# main_board_without_pads.net
KiCad netlist of a schematic drawn in EAGLE
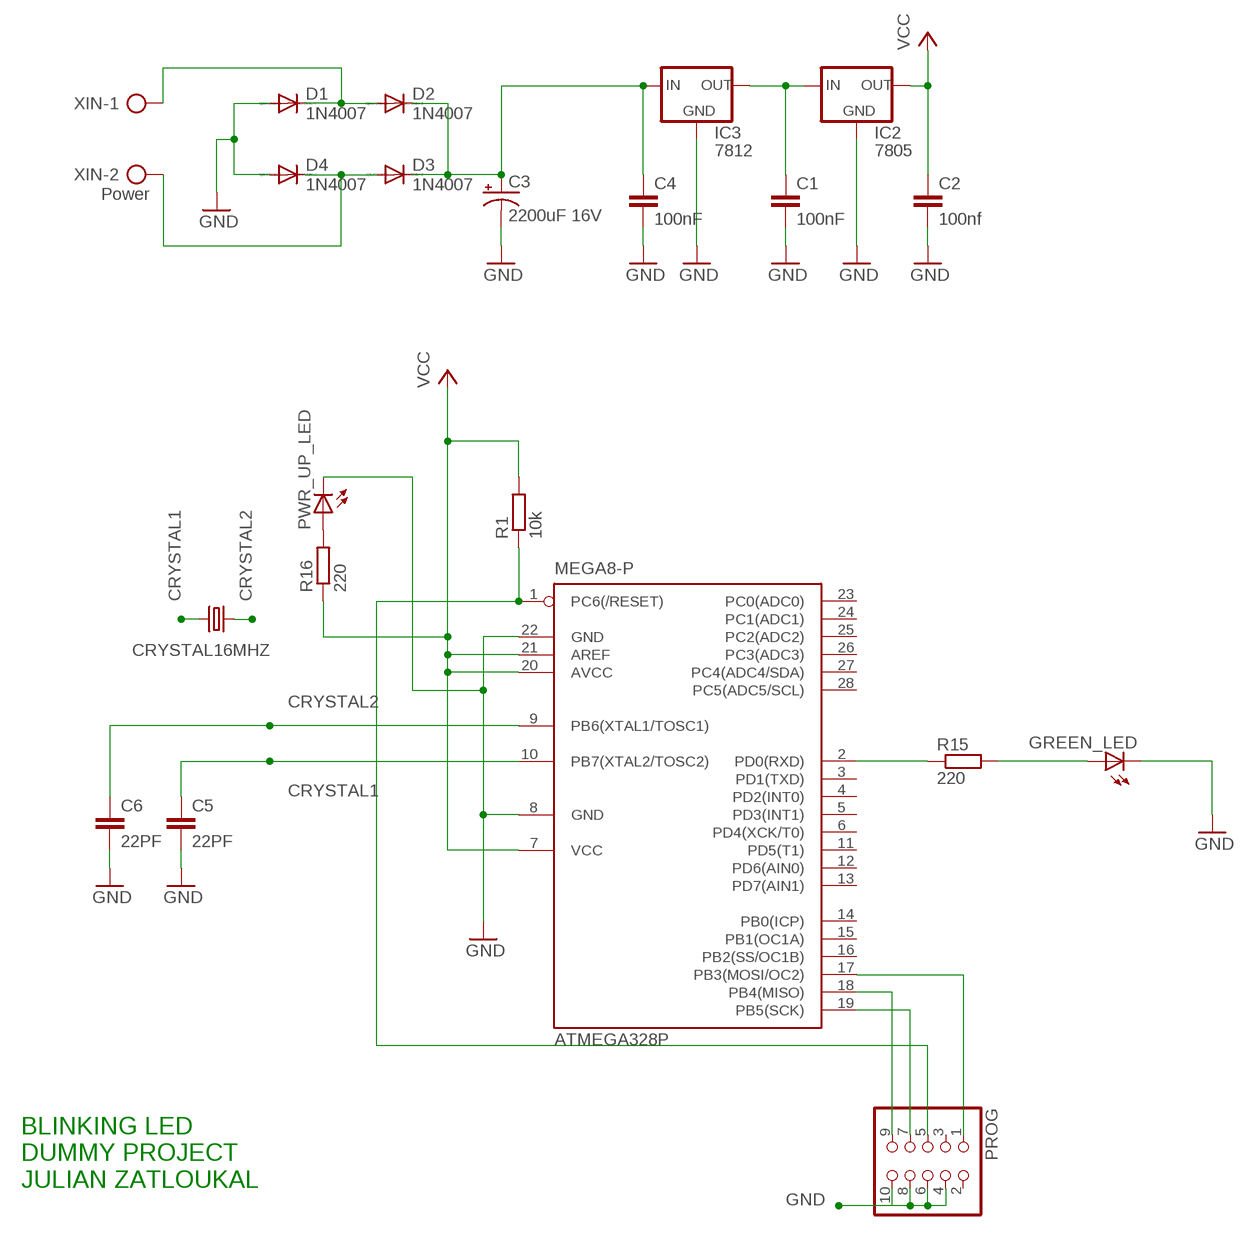
[diagram p0: schematic, sheet 1]

(export (version "E")
  (design (tool "Eeschema 10.0.6"))
  (components
    (comp (ref "ATMEGA328P")
      (value "MEGA8-P")
      (footprint "eagle-import:DIL28-3")
      (libsource (lib "eagle-import") (part "MEGA8-P"))
    )
    (comp (ref "C1")
      (value "100nF")
      (footprint "eagle-import:C050-025X075")
      (libsource (lib "eagle-import") (part "C-EU050-025X075"))
    )
    (comp (ref "C2")
      (value "100nf")
      (footprint "eagle-import:C050-025X075")
      (libsource (lib "eagle-import") (part "C-EU050-025X075"))
    )
    (comp (ref "C3")
      (value "2200uF 16V")
      (footprint "eagle-import:E7,5-16")
      (libsource (lib "eagle-import") (part "CPOL-USE7.5-16"))
    )
    (comp (ref "C4")
      (value "100nF")
      (footprint "eagle-import:C050-025X075")
      (libsource (lib "eagle-import") (part "C-EU050-025X075"))
    )
    (comp (ref "C5")
      (value "22PF")
      (footprint "eagle-import:C050-024X044")
      (libsource (lib "eagle-import") (part "C-EU050-024X044"))
    )
    (comp (ref "C6")
      (value "22PF")
      (footprint "eagle-import:C050-024X044")
      (libsource (lib "eagle-import") (part "C-EU050-024X044"))
    )
    (comp (ref "CRYSTAL16MHZ")
      (value "CRYSTALHC49S")
      (footprint "eagle-import:HC49_S")
      (libsource (lib "eagle-import") (part "CRYSTALHC49S"))
    )
    (comp (ref "D1")
      (value "1N4007")
      (footprint "eagle-import:DO41-10")
      (libsource (lib "eagle-import") (part "1N4004"))
    )
    (comp (ref "D2")
      (value "1N4007")
      (footprint "eagle-import:DO41-10")
      (libsource (lib "eagle-import") (part "1N4004"))
    )
    (comp (ref "D3")
      (value "1N4007")
      (footprint "eagle-import:DO41-10")
      (libsource (lib "eagle-import") (part "1N4004"))
    )
    (comp (ref "D4")
      (value "1N4007")
      (footprint "eagle-import:DO41-10")
      (libsource (lib "eagle-import") (part "1N4004"))
    )
    (comp (ref "GREEN_LED")
      (value "LED5MM")
      (footprint "eagle-import:LED5MM")
      (libsource (lib "eagle-import") (part "LED5MM"))
    )
    (comp (ref "IC2")
      (value "7805")
      (footprint "eagle-import:78XXL")
      (libsource (lib "eagle-import") (part "78XXL"))
    )
    (comp (ref "IC3")
      (value "7812")
      (footprint "eagle-import:78XXL")
      (libsource (lib "eagle-import") (part "78XXL"))
    )
    (comp (ref "PROG")
      (value "PINHD-2X5")
      (footprint "eagle-import:2X05")
      (libsource (lib "eagle-import") (part "PINHD-2X5"))
    )
    (comp (ref "PWR_UP_LED")
      (value "LED5MM")
      (footprint "eagle-import:LED5MM")
      (libsource (lib "eagle-import") (part "LED5MM"))
    )
    (comp (ref "R1")
      (value "10k")
      (footprint "eagle-import:0207_10")
      (libsource (lib "eagle-import") (part "R-EU_0207/10"))
    )
    (comp (ref "R15")
      (value "220")
      (footprint "eagle-import:0207_10")
      (libsource (lib "eagle-import") (part "R-EU_0207/10"))
    )
    (comp (ref "R16")
      (value "220")
      (footprint "eagle-import:0207_10")
      (libsource (lib "eagle-import") (part "rcl_334_R-EU_0207/10"))
    )
    (comp (ref "XIN")
      (value "Power")
      (footprint "eagle-import:AK500_2")
      (libsource (lib "eagle-import") (part "AK500/2"))
    )
  )
  (nets
    (net (code "1") (name "/CRYSTAL1") (class "Default")
      (node (ref "ATMEGA328P") (pin "10") (pinfunction "PB7(XTAL2/TOSC2)_10") (pintype "bidirectional"))
      (node (ref "C5") (pin "1") (pinfunction "1_1") (pintype "passive"))
      (node (ref "CRYSTAL16MHZ") (pin "2") (pinfunction "2_2") (pintype "passive"))
    )
    (net (code "2") (name "/CRYSTAL2") (class "Default")
      (node (ref "ATMEGA328P") (pin "9") (pinfunction "PB6(XTAL1/TOSC1)_9") (pintype "bidirectional"))
      (node (ref "C6") (pin "1") (pinfunction "1_1") (pintype "passive"))
      (node (ref "CRYSTAL16MHZ") (pin "1") (pinfunction "1_1") (pintype "passive"))
    )
    (net (code "3") (name "GND") (class "Default")
      (node (ref "ATMEGA328P") (pin "22") (pinfunction "GND_22") (pintype "power_in"))
      (node (ref "ATMEGA328P") (pin "8") (pinfunction "GND_8") (pintype "power_in"))
      (node (ref "C1") (pin "2") (pinfunction "2_2") (pintype "passive"))
      (node (ref "C2") (pin "2") (pinfunction "2_2") (pintype "passive"))
      (node (ref "C3") (pin "-") (pinfunction "-_-") (pintype "passive"))
      (node (ref "C4") (pin "2") (pinfunction "2_2") (pintype "passive"))
      (node (ref "C5") (pin "2") (pinfunction "2_2") (pintype "passive"))
      (node (ref "C6") (pin "2") (pinfunction "2_2") (pintype "passive"))
      (node (ref "D1") (pin "A") (pinfunction "A_A") (pintype "passive"))
      (node (ref "D4") (pin "A") (pinfunction "A_A") (pintype "passive"))
      (node (ref "GREEN_LED") (pin "K") (pinfunction "C_K") (pintype "passive"))
      (node (ref "IC2") (pin "GND") (pinfunction "GND_GND") (pintype "input"))
      (node (ref "IC3") (pin "GND") (pinfunction "GND_GND") (pintype "input"))
      (node (ref "PROG") (pin "10") (pinfunction "10_10") (pintype "passive"))
      (node (ref "PROG") (pin "4") (pinfunction "4_4") (pintype "passive"))
      (node (ref "PROG") (pin "6") (pinfunction "6_6") (pintype "passive"))
      (node (ref "PROG") (pin "8") (pinfunction "8_8") (pintype "passive"))
      (node (ref "PWR_UP_LED") (pin "K") (pinfunction "C_K") (pintype "passive"))
    )
    (net (code "4") (name "Net-(ATMEGA328P-PB3(MOSI{slash}OC2))") (class "Default")
      (node (ref "ATMEGA328P") (pin "17") (pinfunction "PB3(MOSI/OC2)_17") (pintype "bidirectional"))
      (node (ref "PROG") (pin "1") (pinfunction "1_1") (pintype "passive"))
    )
    (net (code "5") (name "Net-(ATMEGA328P-PB4(MISO))") (class "Default")
      (node (ref "ATMEGA328P") (pin "18") (pinfunction "PB4(MISO)_18") (pintype "bidirectional"))
      (node (ref "PROG") (pin "9") (pinfunction "9_9") (pintype "passive"))
    )
    (net (code "6") (name "Net-(ATMEGA328P-PB5(SCK))") (class "Default")
      (node (ref "ATMEGA328P") (pin "19") (pinfunction "PB5(SCK)_19") (pintype "bidirectional"))
      (node (ref "PROG") (pin "7") (pinfunction "7_7") (pintype "passive"))
    )
    (net (code "7") (name "Net-(ATMEGA328P-PC6({slash}RESET))") (class "Default")
      (node (ref "ATMEGA328P") (pin "1") (pinfunction "PC6(/RESET)_1") (pintype "bidirectional"))
      (node (ref "PROG") (pin "5") (pinfunction "5_5") (pintype "passive"))
      (node (ref "R1") (pin "1") (pinfunction "1_1") (pintype "passive"))
    )
    (net (code "8") (name "Net-(ATMEGA328P-PD0(RXD))") (class "Default")
      (node (ref "ATMEGA328P") (pin "2") (pinfunction "PD0(RXD)_2") (pintype "bidirectional"))
      (node (ref "R15") (pin "1") (pinfunction "1_1") (pintype "passive"))
    )
    (net (code "9") (name "Net-(C1-Pad1)") (class "Default")
      (node (ref "C1") (pin "1") (pinfunction "1_1") (pintype "passive"))
      (node (ref "IC2") (pin "IN") (pinfunction "IN_IN") (pintype "input"))
      (node (ref "IC3") (pin "OUT") (pinfunction "OUT_OUT") (pintype "passive"))
    )
    (net (code "10") (name "Net-(C3-Pad+)") (class "Default")
      (node (ref "C3") (pin "+") (pinfunction "+_+") (pintype "passive"))
      (node (ref "C4") (pin "1") (pinfunction "1_1") (pintype "passive"))
      (node (ref "D2") (pin "C") (pinfunction "C_C") (pintype "passive"))
      (node (ref "D3") (pin "C") (pinfunction "C_C") (pintype "passive"))
      (node (ref "IC3") (pin "IN") (pinfunction "IN_IN") (pintype "input"))
    )
    (net (code "11") (name "Net-(GREEN_LED-PadA)") (class "Default")
      (node (ref "GREEN_LED") (pin "A") (pinfunction "A_A") (pintype "passive"))
      (node (ref "R15") (pin "2") (pinfunction "2_2") (pintype "passive"))
    )
    (net (code "12") (name "Net-(PWR_UP_LED-PadA)") (class "Default")
      (node (ref "PWR_UP_LED") (pin "A") (pinfunction "A_A") (pintype "passive"))
      (node (ref "R16") (pin "2") (pinfunction "2_2") (pintype "passive"))
    )
    (net (code "13") (name "Net-(XINA-KL)") (class "Default")
      (node (ref "D1") (pin "C") (pinfunction "C_C") (pintype "passive"))
      (node (ref "D2") (pin "A") (pinfunction "A_A") (pintype "passive"))
      (node (ref "XIN") (pin "1") (pinfunction "KL_1") (pintype "passive"))
    )
    (net (code "14") (name "Net-(XINB-KL)") (class "Default")
      (node (ref "D3") (pin "A") (pinfunction "A_A") (pintype "passive"))
      (node (ref "D4") (pin "C") (pinfunction "C_C") (pintype "passive"))
      (node (ref "XIN") (pin "2") (pinfunction "KL_2") (pintype "passive"))
    )
    (net (code "15") (name "VCC") (class "Default")
      (node (ref "ATMEGA328P") (pin "20") (pinfunction "AVCC_20") (pintype "power_in"))
      (node (ref "ATMEGA328P") (pin "21") (pinfunction "AREF_21") (pintype "passive"))
      (node (ref "ATMEGA328P") (pin "7") (pinfunction "VCC_7") (pintype "power_in"))
      (node (ref "C2") (pin "1") (pinfunction "1_1") (pintype "passive"))
      (node (ref "IC2") (pin "OUT") (pinfunction "OUT_OUT") (pintype "passive"))
      (node (ref "R1") (pin "2") (pinfunction "2_2") (pintype "passive"))
      (node (ref "R16") (pin "1") (pinfunction "1_1") (pintype "passive"))
    )
    (net (code "16") (name "unconnected-(ATMEGA328P-PB0(ICP)-Pad14)") (class "Default")
      (node (ref "ATMEGA328P") (pin "14") (pinfunction "PB0(ICP)_14") (pintype "bidirectional"))
    )
    (net (code "17") (name "unconnected-(ATMEGA328P-PB1(OC1A)-Pad15)") (class "Default")
      (node (ref "ATMEGA328P") (pin "15") (pinfunction "PB1(OC1A)_15") (pintype "bidirectional"))
    )
    (net (code "18") (name "unconnected-(ATMEGA328P-PB2(SS{slash}OC1B)-Pad16)") (class "Default")
      (node (ref "ATMEGA328P") (pin "16") (pinfunction "PB2(SS/OC1B)_16") (pintype "bidirectional"))
    )
    (net (code "19") (name "unconnected-(ATMEGA328P-PC0(ADC0)-Pad23)") (class "Default")
      (node (ref "ATMEGA328P") (pin "23") (pinfunction "PC0(ADC0)_23") (pintype "bidirectional"))
    )
    (net (code "20") (name "unconnected-(ATMEGA328P-PC1(ADC1)-Pad24)") (class "Default")
      (node (ref "ATMEGA328P") (pin "24") (pinfunction "PC1(ADC1)_24") (pintype "bidirectional"))
    )
    (net (code "21") (name "unconnected-(ATMEGA328P-PC2(ADC2)-Pad25)") (class "Default")
      (node (ref "ATMEGA328P") (pin "25") (pinfunction "PC2(ADC2)_25") (pintype "bidirectional"))
    )
    (net (code "22") (name "unconnected-(ATMEGA328P-PC3(ADC3)-Pad26)") (class "Default")
      (node (ref "ATMEGA328P") (pin "26") (pinfunction "PC3(ADC3)_26") (pintype "bidirectional"))
    )
    (net (code "23") (name "unconnected-(ATMEGA328P-PC4(ADC4{slash}SDA)-Pad27)") (class "Default")
      (node (ref "ATMEGA328P") (pin "27") (pinfunction "PC4(ADC4/SDA)_27") (pintype "bidirectional"))
    )
    (net (code "24") (name "unconnected-(ATMEGA328P-PC5(ADC5{slash}SCL)-Pad28)") (class "Default")
      (node (ref "ATMEGA328P") (pin "28") (pinfunction "PC5(ADC5/SCL)_28") (pintype "bidirectional"))
    )
    (net (code "25") (name "unconnected-(ATMEGA328P-PD1(TXD)-Pad3)") (class "Default")
      (node (ref "ATMEGA328P") (pin "3") (pinfunction "PD1(TXD)_3") (pintype "bidirectional"))
    )
    (net (code "26") (name "unconnected-(ATMEGA328P-PD2(INT0)-Pad4)") (class "Default")
      (node (ref "ATMEGA328P") (pin "4") (pinfunction "PD2(INT0)_4") (pintype "bidirectional"))
    )
    (net (code "27") (name "unconnected-(ATMEGA328P-PD3(INT1)-Pad5)") (class "Default")
      (node (ref "ATMEGA328P") (pin "5") (pinfunction "PD3(INT1)_5") (pintype "bidirectional"))
    )
    (net (code "28") (name "unconnected-(ATMEGA328P-PD4(XCK{slash}T0)-Pad6)") (class "Default")
      (node (ref "ATMEGA328P") (pin "6") (pinfunction "PD4(XCK/T0)_6") (pintype "bidirectional"))
    )
    (net (code "29") (name "unconnected-(ATMEGA328P-PD5(T1)-Pad11)") (class "Default")
      (node (ref "ATMEGA328P") (pin "11") (pinfunction "PD5(T1)_11") (pintype "bidirectional"))
    )
    (net (code "30") (name "unconnected-(ATMEGA328P-PD6(AIN0)-Pad12)") (class "Default")
      (node (ref "ATMEGA328P") (pin "12") (pinfunction "PD6(AIN0)_12") (pintype "bidirectional"))
    )
    (net (code "31") (name "unconnected-(ATMEGA328P-PD7(AIN1)-Pad13)") (class "Default")
      (node (ref "ATMEGA328P") (pin "13") (pinfunction "PD7(AIN1)_13") (pintype "bidirectional"))
    )
    (net (code "32") (name "unconnected-(PROG-Pad2)") (class "Default")
      (node (ref "PROG") (pin "2") (pinfunction "2_2") (pintype "passive"))
    )
    (net (code "33") (name "unconnected-(PROG-Pad3)") (class "Default")
      (node (ref "PROG") (pin "3") (pinfunction "3_3") (pintype "passive"))
    )
  )
)
